# 89c51.net
KiCad netlist of a schematic drawn in Altium Designer
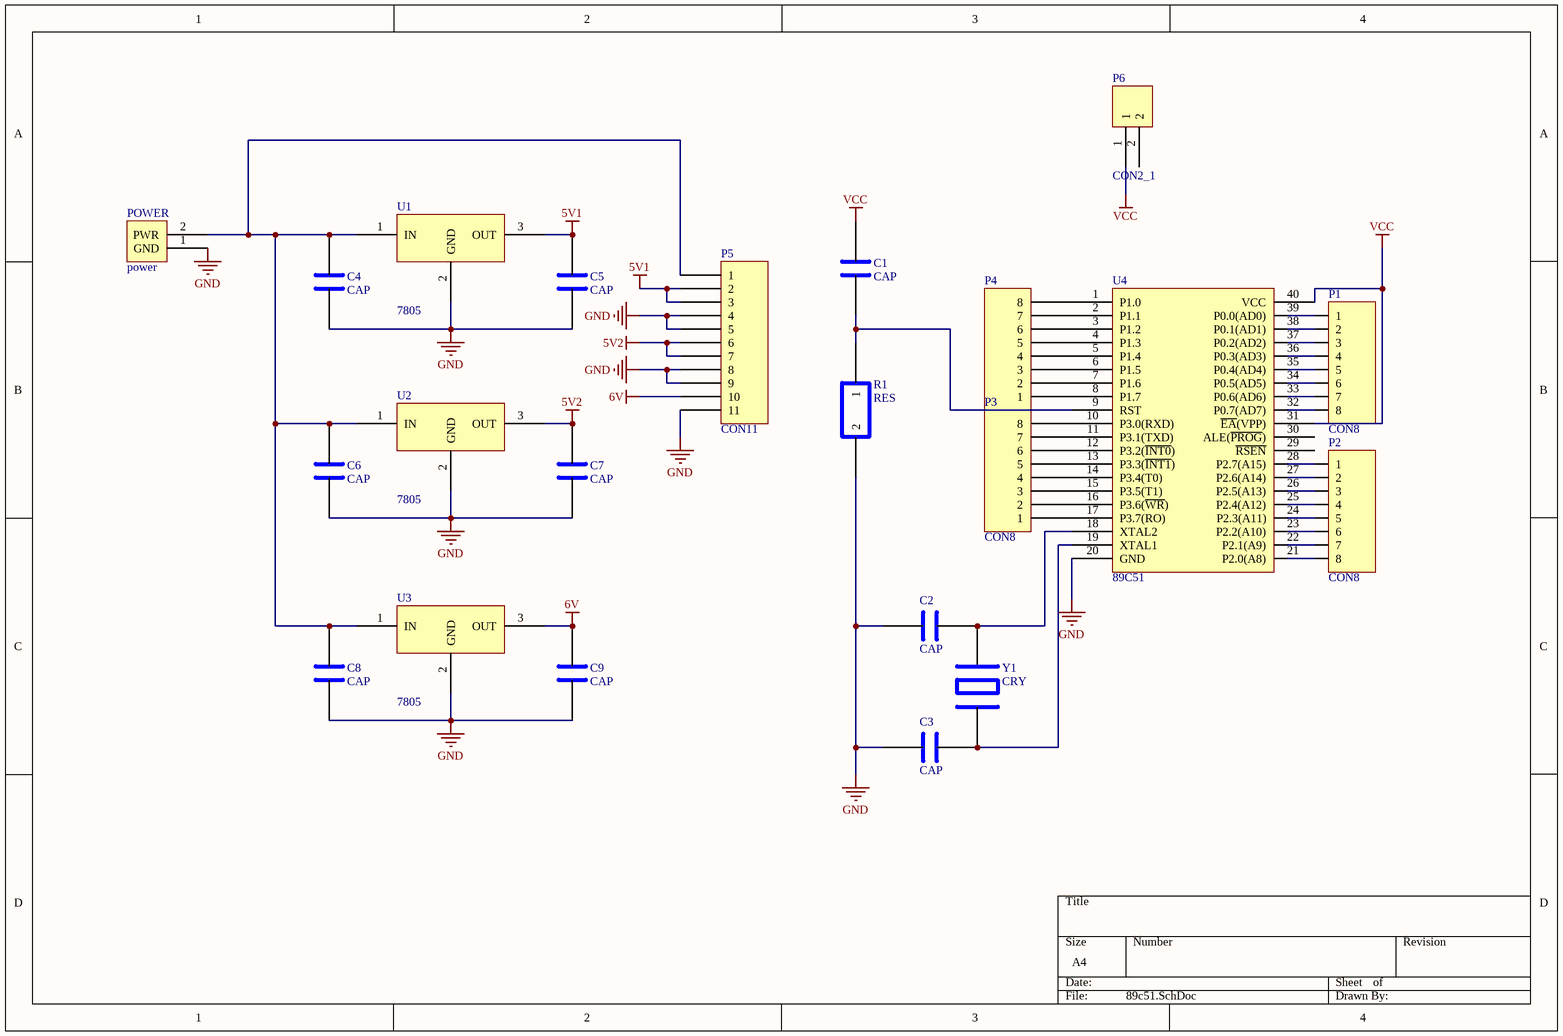
[diagram p0: 89c51.SchDoc]

(export (version "E")
  (design (tool "Eeschema 10.0.6"))
  (components
    (comp (ref "C1") (value "CAP") (libsource (lib "89C51") (part "CAP")))
    (comp (ref "C2") (value "CAP") (libsource (lib "89C51") (part "CAP")))
    (comp (ref "C3") (value "CAP") (libsource (lib "89C51") (part "CAP")))
    (comp (ref "C4") (value "CAP") (libsource (lib "89C51") (part "CAP")))
    (comp (ref "C5") (value "CAP") (libsource (lib "89C51") (part "CAP")))
    (comp (ref "C6") (value "CAP") (libsource (lib "89C51") (part "CAP")))
    (comp (ref "C7") (value "CAP") (libsource (lib "89C51") (part "CAP")))
    (comp (ref "C8") (value "CAP") (libsource (lib "89C51") (part "CAP")))
    (comp (ref "C9") (value "CAP") (libsource (lib "89C51") (part "CAP")))
    (comp (ref "P1") (value "CON8") (libsource (lib "89C51") (part "CON8")))
    (comp (ref "P2") (value "CON8") (libsource (lib "89C51") (part "CON8")))
    (comp (ref "P3") (value "CON8") (libsource (lib "") (part "CON8_1")))
    (comp (ref "P4") (value "CON8") (libsource (lib "") (part "CON8_1")))
    (comp (ref "P5") (value "CON11") (libsource (lib "89C51") (part "COM11")))
    (comp (ref "P6") (value "CON2_1") (footprint "HDR1X2") (libsource (lib "89C51") (part "COM2_1")))
    (comp (ref "POWER") (value "power") (libsource (lib "89C51") (part "CON2")))
    (comp (ref "R1") (value "RES") (libsource (lib "89C51") (part "RES")))
    (comp (ref "U1") (value "7805") (libsource (lib "89C51") (part "7805")))
    (comp (ref "U2") (value "7805") (libsource (lib "89C51") (part "7805")))
    (comp (ref "U3") (value "7805") (libsource (lib "89C51") (part "7805")))
    (comp (ref "U4") (value "89C51") (libsource (lib "89C51") (part "89C51")))
    (comp (ref "Y1") (value "CRY") (libsource (lib "89C51") (part "CRY")))
  )
  (nets
    (net (code "1") (name "5V1") (class "Default")
      (node (ref "C5") (pin "1") (pinfunction "IN_1") (pintype "passive"))
      (node (ref "P5") (pin "2") (pinfunction "2_2") (pintype "passive"))
      (node (ref "P5") (pin "3") (pinfunction "3_3") (pintype "passive"))
      (node (ref "U1") (pin "3") (pinfunction "OUT_3") (pintype "passive"))
    )
    (net (code "2") (name "5V2") (class "Default")
      (node (ref "C7") (pin "1") (pinfunction "IN_1") (pintype "passive"))
      (node (ref "P5") (pin "6") (pinfunction "6_6") (pintype "passive"))
      (node (ref "P5") (pin "7") (pinfunction "7_7") (pintype "passive"))
      (node (ref "U2") (pin "3") (pinfunction "OUT_3") (pintype "passive"))
    )
    (net (code "3") (name "6V") (class "Default")
      (node (ref "C9") (pin "1") (pinfunction "IN_1") (pintype "passive"))
      (node (ref "P5") (pin "10") (pinfunction "10_10") (pintype "passive"))
      (node (ref "U3") (pin "3") (pinfunction "OUT_3") (pintype "passive"))
    )
    (net (code "4") (name "GND") (class "Default")
      (node (ref "C2") (pin "1") (pinfunction "IN_1") (pintype "passive"))
      (node (ref "C3") (pin "1") (pinfunction "IN_1") (pintype "passive"))
      (node (ref "C4") (pin "2") (pinfunction "IN_2") (pintype "passive"))
      (node (ref "C5") (pin "2") (pinfunction "IN_2") (pintype "passive"))
      (node (ref "C6") (pin "2") (pinfunction "IN_2") (pintype "passive"))
      (node (ref "C7") (pin "2") (pinfunction "IN_2") (pintype "passive"))
      (node (ref "C8") (pin "2") (pinfunction "IN_2") (pintype "passive"))
      (node (ref "C9") (pin "2") (pinfunction "IN_2") (pintype "passive"))
      (node (ref "P5") (pin "11") (pinfunction "11_11") (pintype "passive"))
      (node (ref "P5") (pin "4") (pinfunction "4_4") (pintype "passive"))
      (node (ref "P5") (pin "5") (pinfunction "5_5") (pintype "passive"))
      (node (ref "P5") (pin "8") (pinfunction "8_8") (pintype "passive"))
      (node (ref "P5") (pin "9") (pinfunction "9_9") (pintype "passive"))
      (node (ref "POWER") (pin "1") (pinfunction "GND_1") (pintype "passive"))
      (node (ref "R1") (pin "2") (pinfunction "2_2") (pintype "passive"))
      (node (ref "U1") (pin "2") (pinfunction "GND_2") (pintype "passive"))
      (node (ref "U2") (pin "2") (pinfunction "GND_2") (pintype "passive"))
      (node (ref "U3") (pin "2") (pinfunction "GND_2") (pintype "passive"))
      (node (ref "U4") (pin "20") (pinfunction "GND_20") (pintype "passive"))
    )
    (net (code "5") (name "Net-(POWER-PWR)") (class "Default")
      (node (ref "C4") (pin "1") (pinfunction "IN_1") (pintype "passive"))
      (node (ref "C6") (pin "1") (pinfunction "IN_1") (pintype "passive"))
      (node (ref "C8") (pin "1") (pinfunction "IN_1") (pintype "passive"))
      (node (ref "P5") (pin "1") (pinfunction "1_1") (pintype "passive"))
      (node (ref "POWER") (pin "2") (pinfunction "PWR_2") (pintype "passive"))
      (node (ref "U1") (pin "1") (pinfunction "IN_1") (pintype "passive"))
      (node (ref "U2") (pin "1") (pinfunction "IN_1") (pintype "passive"))
      (node (ref "U3") (pin "1") (pinfunction "IN_1") (pintype "passive"))
    )
    (net (code "6") (name "Net-(U4-P0.0(AD0))") (class "Default")
      (node (ref "P1") (pin "1") (pinfunction "1_1") (pintype "passive"))
      (node (ref "U4") (pin "39") (pinfunction "P0.0(AD0)_39") (pintype "passive"))
    )
    (net (code "7") (name "Net-(U4-P0.1(AD1))") (class "Default")
      (node (ref "P1") (pin "2") (pinfunction "2_2") (pintype "passive"))
      (node (ref "U4") (pin "38") (pinfunction "P0.1(AD1)_38") (pintype "passive"))
    )
    (net (code "8") (name "Net-(U4-P0.2(AD2))") (class "Default")
      (node (ref "P1") (pin "3") (pinfunction "3_3") (pintype "passive"))
      (node (ref "U4") (pin "37") (pinfunction "P0.2(AD2)_37") (pintype "passive"))
    )
    (net (code "9") (name "Net-(U4-P0.3(AD3))") (class "Default")
      (node (ref "P1") (pin "4") (pinfunction "4_4") (pintype "passive"))
      (node (ref "U4") (pin "36") (pinfunction "P0.3(AD3)_36") (pintype "passive"))
    )
    (net (code "10") (name "Net-(U4-P0.4(AD4))") (class "Default")
      (node (ref "P1") (pin "5") (pinfunction "5_5") (pintype "passive"))
      (node (ref "U4") (pin "35") (pinfunction "P0.4(AD4)_35") (pintype "passive"))
    )
    (net (code "11") (name "Net-(U4-P0.5(AD5))") (class "Default")
      (node (ref "P1") (pin "6") (pinfunction "6_6") (pintype "passive"))
      (node (ref "U4") (pin "34") (pinfunction "P0.5(AD5)_34") (pintype "passive"))
    )
    (net (code "12") (name "Net-(U4-P0.6(AD6))") (class "Default")
      (node (ref "P1") (pin "7") (pinfunction "7_7") (pintype "passive"))
      (node (ref "U4") (pin "33") (pinfunction "P0.6(AD6)_33") (pintype "passive"))
    )
    (net (code "13") (name "Net-(U4-P0.7(AD7))") (class "Default")
      (node (ref "P1") (pin "8") (pinfunction "8_8") (pintype "passive"))
      (node (ref "U4") (pin "32") (pinfunction "P0.7(AD7)_32") (pintype "passive"))
    )
    (net (code "14") (name "Net-(U4-P1.0)") (class "Default")
      (node (ref "P4") (pin "8") (pinfunction "8_8") (pintype "passive"))
      (node (ref "U4") (pin "1") (pinfunction "P1.0_1") (pintype "passive"))
    )
    (net (code "15") (name "Net-(U4-P1.1)") (class "Default")
      (node (ref "P4") (pin "7") (pinfunction "7_7") (pintype "passive"))
      (node (ref "U4") (pin "2") (pinfunction "P1.1_2") (pintype "passive"))
    )
    (net (code "16") (name "Net-(U4-P1.2)") (class "Default")
      (node (ref "P4") (pin "6") (pinfunction "6_6") (pintype "passive"))
      (node (ref "U4") (pin "3") (pinfunction "P1.2_3") (pintype "passive"))
    )
    (net (code "17") (name "Net-(U4-P1.3)") (class "Default")
      (node (ref "P4") (pin "5") (pinfunction "5_5") (pintype "passive"))
      (node (ref "U4") (pin "4") (pinfunction "P1.3_4") (pintype "passive"))
    )
    (net (code "18") (name "Net-(U4-P1.4)") (class "Default")
      (node (ref "P4") (pin "4") (pinfunction "4_4") (pintype "passive"))
      (node (ref "U4") (pin "5") (pinfunction "P1.4_5") (pintype "passive"))
    )
    (net (code "19") (name "Net-(U4-P1.5)") (class "Default")
      (node (ref "P4") (pin "3") (pinfunction "3_3") (pintype "passive"))
      (node (ref "U4") (pin "6") (pinfunction "P1.5_6") (pintype "passive"))
    )
    (net (code "20") (name "Net-(U4-P1.6)") (class "Default")
      (node (ref "P4") (pin "2") (pinfunction "2_2") (pintype "passive"))
      (node (ref "U4") (pin "7") (pinfunction "P1.6_7") (pintype "passive"))
    )
    (net (code "21") (name "Net-(U4-P1.7)") (class "Default")
      (node (ref "P4") (pin "1") (pinfunction "1_1") (pintype "passive"))
      (node (ref "U4") (pin "8") (pinfunction "P1.7_8") (pintype "passive"))
    )
    (net (code "22") (name "Net-(U4-P2.0(A8))") (class "Default")
      (node (ref "P2") (pin "8") (pinfunction "8_8") (pintype "passive"))
      (node (ref "U4") (pin "21") (pinfunction "P2.0(A8)_21") (pintype "passive"))
    )
    (net (code "23") (name "Net-(U4-P2.1(A9))") (class "Default")
      (node (ref "P2") (pin "7") (pinfunction "7_7") (pintype "passive"))
      (node (ref "U4") (pin "22") (pinfunction "P2.1(A9)_22") (pintype "passive"))
    )
    (net (code "24") (name "Net-(U4-P2.2(A10))") (class "Default")
      (node (ref "P2") (pin "6") (pinfunction "6_6") (pintype "passive"))
      (node (ref "U4") (pin "23") (pinfunction "P2.2(A10)_23") (pintype "passive"))
    )
    (net (code "25") (name "Net-(U4-P2.3(A11))") (class "Default")
      (node (ref "P2") (pin "5") (pinfunction "5_5") (pintype "passive"))
      (node (ref "U4") (pin "24") (pinfunction "P2.3(A11)_24") (pintype "passive"))
    )
    (net (code "26") (name "Net-(U4-P2.4(A12))") (class "Default")
      (node (ref "P2") (pin "4") (pinfunction "4_4") (pintype "passive"))
      (node (ref "U4") (pin "25") (pinfunction "P2.4(A12)_25") (pintype "passive"))
    )
    (net (code "27") (name "Net-(U4-P2.5(A13))") (class "Default")
      (node (ref "P2") (pin "3") (pinfunction "3_3") (pintype "passive"))
      (node (ref "U4") (pin "26") (pinfunction "P2.5(A13)_26") (pintype "passive"))
    )
    (net (code "28") (name "Net-(U4-P2.6(A14))") (class "Default")
      (node (ref "P2") (pin "2") (pinfunction "2_2") (pintype "passive"))
      (node (ref "U4") (pin "27") (pinfunction "P2.6(A14)_27") (pintype "passive"))
    )
    (net (code "29") (name "Net-(U4-P2.7(A15))") (class "Default")
      (node (ref "P2") (pin "1") (pinfunction "1_1") (pintype "passive"))
      (node (ref "U4") (pin "28") (pinfunction "P2.7(A15)_28") (pintype "passive"))
    )
    (net (code "30") (name "Net-(U4-P3.0(RXD))") (class "Default")
      (node (ref "P3") (pin "8") (pinfunction "8_8") (pintype "passive"))
      (node (ref "U4") (pin "10") (pinfunction "P3.0(RXD)_10") (pintype "passive"))
    )
    (net (code "31") (name "Net-(U4-P3.1(TXD))") (class "Default")
      (node (ref "P3") (pin "7") (pinfunction "7_7") (pintype "passive"))
      (node (ref "U4") (pin "11") (pinfunction "P3.1(TXD)_11") (pintype "passive"))
    )
    (net (code "32") (name "Net-(U4-P3.2(~{INT0}))") (class "Default")
      (node (ref "P3") (pin "6") (pinfunction "6_6") (pintype "passive"))
      (node (ref "U4") (pin "12") (pinfunction "P3.2(~{INT0})_12") (pintype "passive"))
    )
    (net (code "33") (name "Net-(U4-P3.3(~{INT1}))") (class "Default")
      (node (ref "P3") (pin "5") (pinfunction "5_5") (pintype "passive"))
      (node (ref "U4") (pin "13") (pinfunction "P3.3(~{INT1})_13") (pintype "passive"))
    )
    (net (code "34") (name "Net-(U4-P3.4(T0))") (class "Default")
      (node (ref "P3") (pin "4") (pinfunction "4_4") (pintype "passive"))
      (node (ref "U4") (pin "14") (pinfunction "P3.4(T0)_14") (pintype "passive"))
    )
    (net (code "35") (name "Net-(U4-P3.5(T1))") (class "Default")
      (node (ref "P3") (pin "3") (pinfunction "3_3") (pintype "passive"))
      (node (ref "U4") (pin "15") (pinfunction "P3.5(T1)_15") (pintype "passive"))
    )
    (net (code "36") (name "Net-(U4-P3.6(~{WR}))") (class "Default")
      (node (ref "P3") (pin "2") (pinfunction "2_2") (pintype "passive"))
      (node (ref "U4") (pin "16") (pinfunction "P3.6(~{WR})_16") (pintype "passive"))
    )
    (net (code "37") (name "Net-(U4-P3.7(RO))") (class "Default")
      (node (ref "P3") (pin "1") (pinfunction "1_1") (pintype "passive"))
      (node (ref "U4") (pin "17") (pinfunction "P3.7(RO)_17") (pintype "passive"))
    )
    (net (code "38") (name "Net-(U4-RST)") (class "Default")
      (node (ref "C1") (pin "2") (pinfunction "IN_2") (pintype "passive"))
      (node (ref "R1") (pin "1") (pinfunction "1_1") (pintype "passive"))
      (node (ref "U4") (pin "9") (pinfunction "RST_9") (pintype "passive"))
    )
    (net (code "39") (name "Net-(U4-XTAL1)") (class "Default")
      (node (ref "C3") (pin "2") (pinfunction "IN_2") (pintype "passive"))
      (node (ref "U4") (pin "19") (pinfunction "XTAL1_19") (pintype "passive"))
      (node (ref "Y1") (pin "2") (pinfunction "2_2") (pintype "passive"))
    )
    (net (code "40") (name "Net-(U4-XTAL2)") (class "Default")
      (node (ref "C2") (pin "2") (pinfunction "IN_2") (pintype "passive"))
      (node (ref "U4") (pin "18") (pinfunction "XTAL2_18") (pintype "passive"))
      (node (ref "Y1") (pin "1") (pinfunction "1_1") (pintype "passive"))
    )
    (net (code "41") (name "VCC") (class "Default")
      (node (ref "C1") (pin "1") (pinfunction "IN_1") (pintype "passive"))
      (node (ref "P6") (pin "1") (pinfunction "1_1") (pintype "passive"))
      (node (ref "U4") (pin "31") (pinfunction "~{EA}(VPP)_31") (pintype "passive"))
      (node (ref "U4") (pin "40") (pinfunction "VCC_40") (pintype "passive"))
    )
    (net (code "42") (name "unconnected-(P6-Pad2)") (class "Default")
      (node (ref "P6") (pin "2") (pinfunction "2_2") (pintype "passive"))
    )
    (net (code "43") (name "unconnected-(U4-ALE(~{PROG})-Pad30)") (class "Default")
      (node (ref "U4") (pin "30") (pinfunction "ALE(~{PROG})_30") (pintype "passive"))
    )
    (net (code "44") (name "unconnected-(U4-~{RSEN}-Pad29)") (class "Default")
      (node (ref "U4") (pin "29") (pinfunction "~{RSEN}_29") (pintype "passive"))
    )
  )
)
